# npm1300_qeaa_config3.net
KiCad netlist of a schematic drawn in Altium Designer
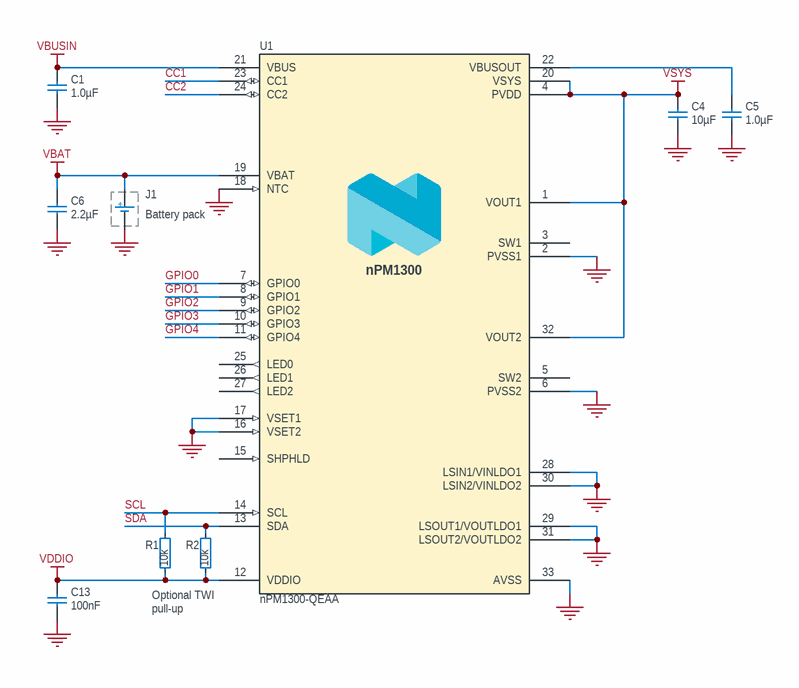
[diagram p0: npm1300_qeaa_config3.SchDoc]

(export (version "E")
  (design (tool "Eeschema 10.0.6"))
  (components
    (comp (ref "C1")
      (value "1.0µF")
      (footprint "CAPC1608X06L")
      (description "Capacitor, Ceramic, 1.0µF 10V X5R 0603,±10%")
      (fields
        (field (name "PART NUMBER") "C0603-1µ0-10V-X5R")
        (field (name "MANUFACTURER") "N.A.")
        (field (name "AUTHOR") "getr")
      )
      (libsource (lib "AltiumLib") (part "CAP"))
    )
    (comp (ref "C4")
      (value "10µF")
      (footprint "CAPC1608X06L")
      (description "Capacitor, X5R, ±20%")
      (fields
        (field (name "PART NUMBER") "C0603-10µ")
        (field (name "MANUFACTURER") "N.A.")
        (field (name "AUTHOR") "rsk")
      )
      (libsource (lib "AltiumLib") (part "CAP"))
    )
    (comp (ref "C5")
      (value "1.0µF")
      (footprint "CAPC1608X06L")
      (description "Capacitor, Ceramic, 1.0µF 10V X5R 0603,±10%")
      (fields
        (field (name "PART NUMBER") "C0603-1µ0-10V-X5R")
        (field (name "MANUFACTURER") "N.A.")
        (field (name "AUTHOR") "getr")
      )
      (libsource (lib "AltiumLib") (part "CAP"))
    )
    (comp (ref "C6")
      (value "2.2µF")
      (footprint "CAPC1608X06L")
      (description "Capacitor, Ceramic, X7R, ±10%, 16V")
      (fields
        (field (name "PART NUMBER") "C0603-2.2µ-16V-X7R")
        (field (name "MANUFACTURER") "Taiyo Yuden")
        (field (name "AUTHOR") "rsk")
      )
      (libsource (lib "AltiumLib") (part "CAP"))
    )
    (comp (ref "C13")
      (value "100nF")
      (footprint "CAPC0603X03L_C")
      (description "Capacitor, X5R, ±10%, 100nF, 16V")
      (fields
        (field (name "PART NUMBER") "C0201-100n")
        (field (name "MANUFACTURER") "N.A.")
        (field (name "AUTHOR") "rsk")
      )
      (libsource (lib "AltiumLib") (part "CAP"))
    )
    (comp (ref "J1")
      (value "Battery pack")
      (footprint "TP_2x1mm_TH")
      (fields
        (field (name "PART NUMBER") "Battery_TP")
        (field (name "MANUFACTURER") "N.A.")
        (field (name "AUTHOR") "rsk")
      )
      (libsource (lib "AltiumLib") (part "Battery_pack"))
    )
    (comp (ref "R1")
      (value "10k")
      (footprint "RESC0603X03L_C")
      (description "Resistor, ±1%, 0.05W")
      (fields
        (field (name "PART NUMBER") "R0201-10k")
        (field (name "MANUFACTURER") "N.A.")
        (field (name "AUTHOR") "rsk")
      )
      (libsource (lib "AltiumLib") (part "RES"))
    )
    (comp (ref "R2")
      (value "10k")
      (footprint "RESC0603X03L_C")
      (description "Resistor, ±1%, 0.05W")
      (fields
        (field (name "PART NUMBER") "R0201-10k")
        (field (name "MANUFACTURER") "N.A.")
        (field (name "AUTHOR") "rsk")
      )
      (libsource (lib "AltiumLib") (part "RES"))
    )
    (comp (ref "U1")
      (value "nPM1300-QEAA")
      (footprint "Nordic_QFN50P500X500X90-33N")
      (fields (field (name "MANUFACTURER") "Nordic Semiconductor") (field (name "AUTHOR") "eisk"))
      (libsource (lib "AltiumLib") (part "nPM1300_QEAA"))
    )
  )
  (nets
    (net (code "1") (name "/CC1") (class "Default")
      (node (ref "U1") (pin "23") (pinfunction "CC1_23") (pintype "bidirectional"))
    )
    (net (code "2") (name "/CC2") (class "Default")
      (node (ref "U1") (pin "24") (pinfunction "CC2_24") (pintype "bidirectional"))
    )
    (net (code "3") (name "/GPIO0") (class "Default")
      (node (ref "U1") (pin "7") (pinfunction "GPIO0_7") (pintype "bidirectional"))
    )
    (net (code "4") (name "/GPIO1") (class "Default")
      (node (ref "U1") (pin "8") (pinfunction "GPIO1_8") (pintype "bidirectional"))
    )
    (net (code "5") (name "/GPIO2") (class "Default")
      (node (ref "U1") (pin "9") (pinfunction "GPIO2_9") (pintype "bidirectional"))
    )
    (net (code "6") (name "/GPIO3") (class "Default")
      (node (ref "U1") (pin "10") (pinfunction "GPIO3_10") (pintype "bidirectional"))
    )
    (net (code "7") (name "/GPIO4") (class "Default")
      (node (ref "U1") (pin "11") (pinfunction "GPIO4_11") (pintype "bidirectional"))
    )
    (net (code "8") (name "/SCL") (class "Default")
      (node (ref "R1") (pin "1") (pinfunction "1_1") (pintype "passive"))
      (node (ref "U1") (pin "14") (pinfunction "SCL_14") (pintype "input"))
    )
    (net (code "9") (name "/SDA") (class "Default")
      (node (ref "R2") (pin "1") (pinfunction "1_1") (pintype "passive"))
      (node (ref "U1") (pin "13") (pinfunction "SDA_13") (pintype "open_collector"))
    )
    (net (code "10") (name "GND") (class "Default")
      (node (ref "C1") (pin "1") (pinfunction "1_1") (pintype "passive"))
      (node (ref "C13") (pin "2") (pinfunction "2_2") (pintype "passive"))
      (node (ref "C4") (pin "1") (pinfunction "1_1") (pintype "passive"))
      (node (ref "C5") (pin "1") (pinfunction "1_1") (pintype "passive"))
      (node (ref "C6") (pin "1") (pinfunction "1_1") (pintype "passive"))
      (node (ref "J1") (pin "1") (pinfunction "GND_1") (pintype "passive"))
      (node (ref "U1") (pin "16") (pinfunction "VSET2_16") (pintype "input"))
      (node (ref "U1") (pin "17") (pinfunction "VSET1_17") (pintype "input"))
      (node (ref "U1") (pin "18") (pinfunction "NTC_18") (pintype "input"))
      (node (ref "U1") (pin "2") (pinfunction "PVSS1_2") (pintype "power_in"))
      (node (ref "U1") (pin "28") (pinfunction "LSIN1/VINLDO1_28") (pintype "power_in"))
      (node (ref "U1") (pin "29") (pinfunction "LSOUT1/VOUTLDO1_29") (pintype "power_in"))
      (node (ref "U1") (pin "30") (pinfunction "LSIN2/VINLDO2_30") (pintype "power_in"))
      (node (ref "U1") (pin "31") (pinfunction "LSOUT2/VOUTLDO2_31") (pintype "power_in"))
      (node (ref "U1") (pin "33") (pinfunction "AVSS_33") (pintype "power_in"))
      (node (ref "U1") (pin "6") (pinfunction "PVSS2_6") (pintype "power_in"))
    )
    (net (code "11") (name "Net-(U1-VBUSOUT)") (class "Default")
      (node (ref "C5") (pin "2") (pinfunction "2_2") (pintype "passive"))
      (node (ref "U1") (pin "22") (pinfunction "VBUSOUT_22") (pintype "power_in"))
    )
    (net (code "12") (name "VBAT") (class "Default")
      (node (ref "C6") (pin "2") (pinfunction "2_2") (pintype "passive"))
      (node (ref "J1") (pin "2") (pinfunction "V+_2") (pintype "passive"))
      (node (ref "U1") (pin "19") (pinfunction "VBAT_19") (pintype "passive"))
    )
    (net (code "13") (name "VBUSIN") (class "Default")
      (node (ref "C1") (pin "2") (pinfunction "2_2") (pintype "passive"))
      (node (ref "U1") (pin "21") (pinfunction "VBUS_21") (pintype "power_in"))
    )
    (net (code "14") (name "VDDIO") (class "Default")
      (node (ref "C13") (pin "1") (pinfunction "1_1") (pintype "passive"))
      (node (ref "R1") (pin "2") (pinfunction "2_2") (pintype "passive"))
      (node (ref "R2") (pin "2") (pinfunction "2_2") (pintype "passive"))
      (node (ref "U1") (pin "12") (pinfunction "VDDIO_12") (pintype "power_in"))
    )
    (net (code "15") (name "VSYS") (class "Default")
      (node (ref "C4") (pin "2") (pinfunction "2_2") (pintype "passive"))
      (node (ref "U1") (pin "1") (pinfunction "VOUT1_1") (pintype "power_in"))
      (node (ref "U1") (pin "20") (pinfunction "VSYS_20") (pintype "power_in"))
      (node (ref "U1") (pin "32") (pinfunction "VOUT2_32") (pintype "power_in"))
      (node (ref "U1") (pin "4") (pinfunction "PVDD_4") (pintype "power_in"))
    )
    (net (code "16") (name "unconnected-(U1-LED0-Pad25)") (class "Default")
      (node (ref "U1") (pin "25") (pinfunction "LED0_25") (pintype "output"))
    )
    (net (code "17") (name "unconnected-(U1-LED1-Pad26)") (class "Default")
      (node (ref "U1") (pin "26") (pinfunction "LED1_26") (pintype "output"))
    )
    (net (code "18") (name "unconnected-(U1-LED2-Pad27)") (class "Default")
      (node (ref "U1") (pin "27") (pinfunction "LED2_27") (pintype "output"))
    )
    (net (code "19") (name "unconnected-(U1-SHPHLD-Pad15)") (class "Default")
      (node (ref "U1") (pin "15") (pinfunction "SHPHLD_15") (pintype "input"))
    )
    (net (code "20") (name "unconnected-(U1-SW1-Pad3)") (class "Default")
      (node (ref "U1") (pin "3") (pinfunction "SW1_3") (pintype "power_in"))
    )
    (net (code "21") (name "unconnected-(U1-SW2-Pad5)") (class "Default")
      (node (ref "U1") (pin "5") (pinfunction "SW2_5") (pintype "power_in"))
    )
  )
)
